# mcu_valdis2.net
KiCad netlist of a schematic drawn in Altium Designer
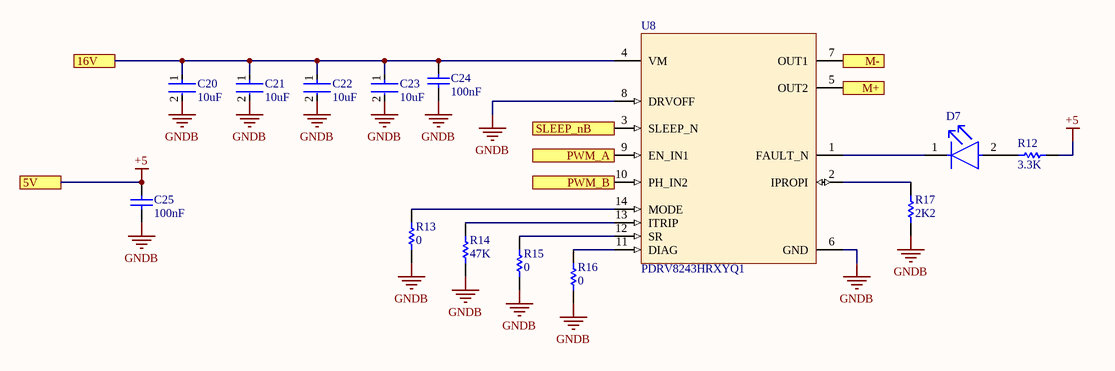
[diagram p0: mcu_valdis2.SchDoc]

(export (version "E")
  (design (tool "Eeschema 10.0.6"))
  (components
    (comp (ref "C20")
      (value "10uF")
      (footprint "FP-CL21-IPC_C")
      (description "CL21 Series 0805 22uF 25V ±20% Tolerance X5R Multilayer Ceramic Chip Capacitor")
      (libsource (lib "Altium Content Vault") (part "b4654b650e69147ec39a6b967a45e02"))
    )
    (comp (ref "C21")
      (value "10uF")
      (footprint "FP-CL21-IPC_C")
      (description "CL21 Series 0805 22uF 25V ±20% Tolerance X5R Multilayer Ceramic Chip Capacitor")
      (libsource (lib "Altium Content Vault") (part "b4654b650e69147ec39a6b967a45e02"))
    )
    (comp (ref "C22")
      (value "10uF")
      (footprint "FP-CL21-IPC_C")
      (description "CL21 Series 0805 22uF 25V ±20% Tolerance X5R Multilayer Ceramic Chip Capacitor")
      (libsource (lib "Altium Content Vault") (part "b4654b650e69147ec39a6b967a45e02"))
    )
    (comp (ref "C23")
      (value "10uF")
      (footprint "FP-CL21-IPC_C")
      (description "CL21 Series 0805 22uF 25V ±20% Tolerance X5R Multilayer Ceramic Chip Capacitor")
      (libsource (lib "Altium Content Vault") (part "b4654b650e69147ec39a6b967a45e02"))
    )
    (comp (ref "C24")
      (value "100nF")
      (footprint "CAPC1608X90X35ML10T15")
      (description "Chip Capacitor, 22 pF, +/- 5%, 50 V, -55 to 125 degC, 0603 (1608 Metric), RoHS, Tape and Reel")
      (fields (field (name "MANUFACTURER") "Murata"))
      (libsource (lib "Altium Content Vault") (part "CAP-NP-2"))
    )
    (comp (ref "C25")
      (value "100nF")
      (footprint "CAPC1608X90X35ML10T15")
      (description "Chip Capacitor, 22 pF, +/- 5%, 50 V, -55 to 125 degC, 0603 (1608 Metric), RoHS, Tape and Reel")
      (fields (field (name "MANUFACTURER") "Murata"))
      (libsource (lib "Altium Content Vault") (part "CAP-NP-2"))
    )
    (comp (ref "D7")
      (value "LTST-C191TBKT")
      (footprint "FP-LTST-C191TBKT-MFG")
      (description "LED BLUE CLEAR CHIP SMD")
      (libsource (lib "Altium Content Vault") (part "8706943c75ba83719d021d2fdc84c58"))
    )
    (comp (ref "R12")
      (value "3.3K")
      (footprint "RESC1609X50X30NL8T20")
      (description "Chip Resistor, 0 Ohm, Jumper, 100 mW, -55 to 155 degC, 0603 (1608 Metric), RoHS, Tape and Reel")
      (fields (field (name "MANUFACTURER") "Vishay Semiconductor"))
      (libsource (lib "Altium Content Vault") (part "RES-2"))
    )
    (comp (ref "R13")
      (value "0")
      (footprint "RESC1609X50X30NL8T20")
      (description "Chip Resistor, 0 Ohm, Jumper, 100 mW, -55 to 155 degC, 0603 (1608 Metric), RoHS, Tape and Reel")
      (fields (field (name "MANUFACTURER") "Vishay Semiconductor"))
      (libsource (lib "Altium Content Vault") (part "RES-2"))
    )
    (comp (ref "R14")
      (value "47K")
      (footprint "RESC1609X50X30NL8T20")
      (description "Chip Resistor, 0 Ohm, Jumper, 100 mW, -55 to 155 degC, 0603 (1608 Metric), RoHS, Tape and Reel")
      (fields (field (name "MANUFACTURER") "Vishay Semiconductor"))
      (libsource (lib "Altium Content Vault") (part "RES-2"))
    )
    (comp (ref "R15")
      (value "0")
      (footprint "RESC1609X50X30NL8T20")
      (description "Chip Resistor, 0 Ohm, Jumper, 100 mW, -55 to 155 degC, 0603 (1608 Metric), RoHS, Tape and Reel")
      (fields (field (name "MANUFACTURER") "Vishay Semiconductor"))
      (libsource (lib "Altium Content Vault") (part "RES-2"))
    )
    (comp (ref "R16")
      (value "0")
      (footprint "RESC1609X50X30NL8T20")
      (description "Chip Resistor, 0 Ohm, Jumper, 100 mW, -55 to 155 degC, 0603 (1608 Metric), RoHS, Tape and Reel")
      (fields (field (name "MANUFACTURER") "Vishay Semiconductor"))
      (libsource (lib "Altium Content Vault") (part "RES-2"))
    )
    (comp (ref "R17")
      (value "2K2")
      (footprint "RESC1609X50X30NL8T20")
      (description "Chip Resistor, 0 Ohm, Jumper, 100 mW, -55 to 155 degC, 0603 (1608 Metric), RoHS, Tape and Reel")
      (fields (field (name "MANUFACTURER") "Vishay Semiconductor"))
      (libsource (lib "Altium Content Vault") (part "RES-2"))
    )
    (comp (ref "U8")
      (value "PDRV8243HRXYQ1")
      (footprint "RXY0014A-MFG")
      (description "No Description Available")
      (fields (field (name "COPYRIGHT") "Copyright (C) 2022 Ultra Librarian. All rights reserved."))
      (libsource (lib "Valdis_Components") (part "PDRV8243HRXYQ1"))
    )
  )
  (nets
    (net (code "1") (name "+5") (class "Default")
      (node (ref "C25") (pin "2") (pinfunction "2_2") (pintype "passive"))
      (node (ref "R12") (pin "2") (pinfunction "2_2") (pintype "passive"))
    )
    (net (code "2") (name "/16V") (class "Default")
      (node (ref "C20") (pin "1") (pinfunction "1_1") (pintype "passive"))
      (node (ref "C21") (pin "1") (pinfunction "1_1") (pintype "passive"))
      (node (ref "C22") (pin "1") (pinfunction "1_1") (pintype "passive"))
      (node (ref "C23") (pin "1") (pinfunction "1_1") (pintype "passive"))
      (node (ref "C24") (pin "2") (pinfunction "2_2") (pintype "passive"))
      (node (ref "U8") (pin "4") (pinfunction "VM_4") (pintype "power_in"))
    )
    (net (code "3") (name "/M+") (class "Default")
      (node (ref "U8") (pin "5") (pinfunction "OUT2_5") (pintype "passive"))
    )
    (net (code "4") (name "/M-") (class "Default")
      (node (ref "U8") (pin "7") (pinfunction "OUT1_7") (pintype "passive"))
    )
    (net (code "5") (name "/PWM_A") (class "Default")
      (node (ref "U8") (pin "9") (pinfunction "EN_IN1_9") (pintype "input"))
    )
    (net (code "6") (name "/PWM_B") (class "Default")
      (node (ref "U8") (pin "10") (pinfunction "PH_IN2_10") (pintype "input"))
    )
    (net (code "7") (name "/SLEEP_nB") (class "Default")
      (node (ref "U8") (pin "3") (pinfunction "SLEEP_N_3") (pintype "input"))
    )
    (net (code "8") (name "GNDB") (class "Default")
      (node (ref "C20") (pin "2") (pinfunction "2_2") (pintype "passive"))
      (node (ref "C21") (pin "2") (pinfunction "2_2") (pintype "passive"))
      (node (ref "C22") (pin "2") (pinfunction "2_2") (pintype "passive"))
      (node (ref "C23") (pin "2") (pinfunction "2_2") (pintype "passive"))
      (node (ref "C24") (pin "1") (pinfunction "1_1") (pintype "passive"))
      (node (ref "C25") (pin "1") (pinfunction "1_1") (pintype "passive"))
      (node (ref "R13") (pin "1") (pinfunction "1_1") (pintype "passive"))
      (node (ref "R14") (pin "1") (pinfunction "1_1") (pintype "passive"))
      (node (ref "R15") (pin "1") (pinfunction "1_1") (pintype "passive"))
      (node (ref "R16") (pin "1") (pinfunction "1_1") (pintype "passive"))
      (node (ref "R17") (pin "1") (pinfunction "1_1") (pintype "passive"))
      (node (ref "U8") (pin "6") (pinfunction "GND_6") (pintype "power_in"))
      (node (ref "U8") (pin "8") (pinfunction "DRVOFF_8") (pintype "input"))
    )
    (net (code "9") (name "Net-(D7-A)") (class "Default")
      (node (ref "D7") (pin "2") (pinfunction "A_2") (pintype "passive"))
      (node (ref "R12") (pin "1") (pinfunction "1_1") (pintype "passive"))
    )
    (net (code "10") (name "Net-(D7-C)") (class "Default")
      (node (ref "D7") (pin "1") (pinfunction "C_1") (pintype "passive"))
      (node (ref "U8") (pin "1") (pinfunction "FAULT_N_1") (pintype "open_collector"))
    )
    (net (code "11") (name "Net-(U8-DIAG)") (class "Default")
      (node (ref "R16") (pin "2") (pinfunction "2_2") (pintype "passive"))
      (node (ref "U8") (pin "11") (pinfunction "DIAG_11") (pintype "input"))
    )
    (net (code "12") (name "Net-(U8-IPROPI)") (class "Default")
      (node (ref "R17") (pin "2") (pinfunction "2_2") (pintype "passive"))
      (node (ref "U8") (pin "2") (pinfunction "IPROPI_2") (pintype "bidirectional"))
    )
    (net (code "13") (name "Net-(U8-ITRIP)") (class "Default")
      (node (ref "R14") (pin "2") (pinfunction "2_2") (pintype "passive"))
      (node (ref "U8") (pin "13") (pinfunction "ITRIP_13") (pintype "input"))
    )
    (net (code "14") (name "Net-(U8-MODE)") (class "Default")
      (node (ref "R13") (pin "2") (pinfunction "2_2") (pintype "passive"))
      (node (ref "U8") (pin "14") (pinfunction "MODE_14") (pintype "input"))
    )
    (net (code "15") (name "Net-(U8-SR)") (class "Default")
      (node (ref "R15") (pin "2") (pinfunction "2_2") (pintype "passive"))
      (node (ref "U8") (pin "12") (pinfunction "SR_12") (pintype "input"))
    )
  )
)
